# v0_3_0.net
KiCad netlist of a schematic drawn in EAGLE
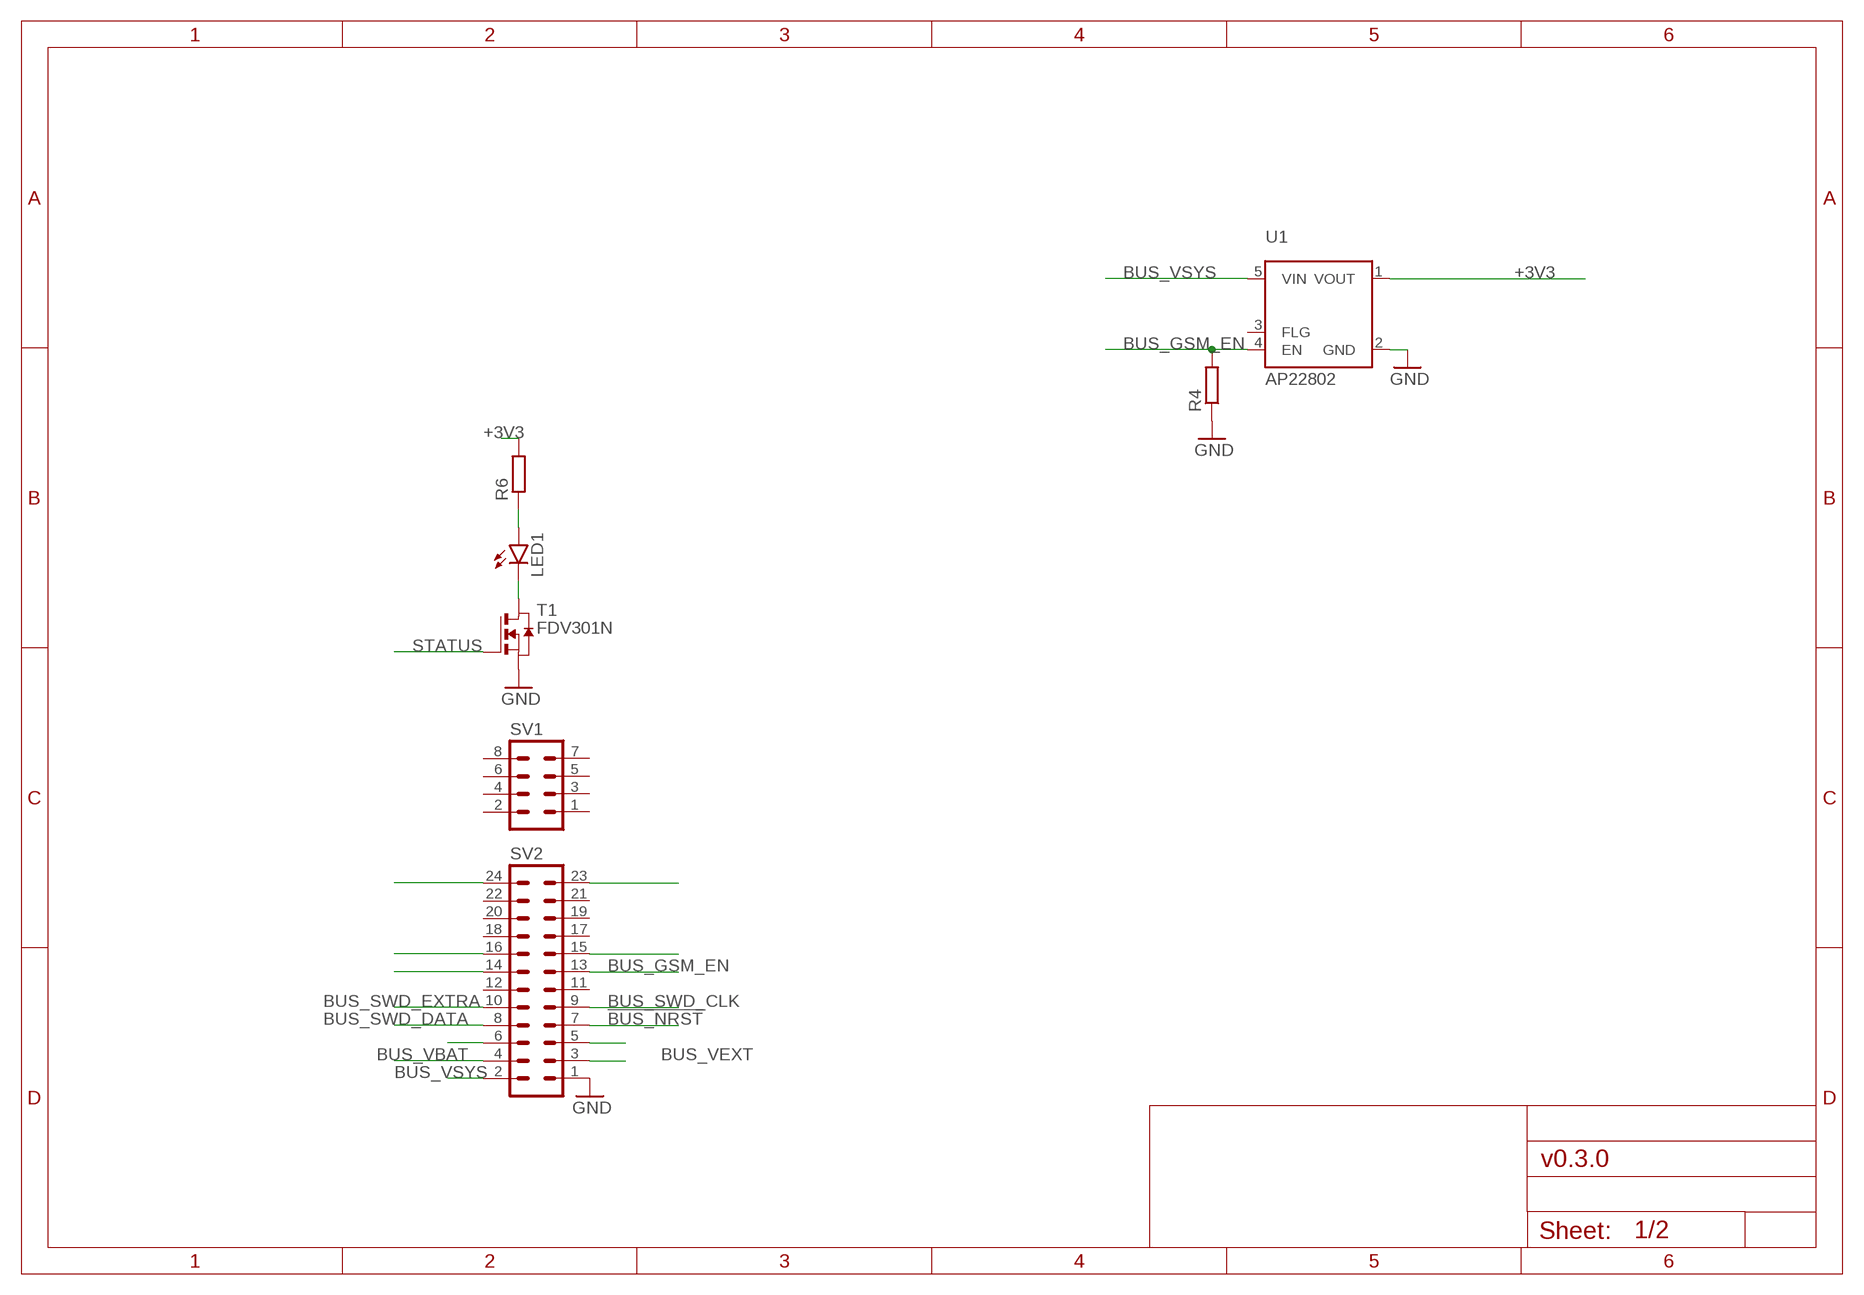
[diagram p0: schematic, sheet 1]
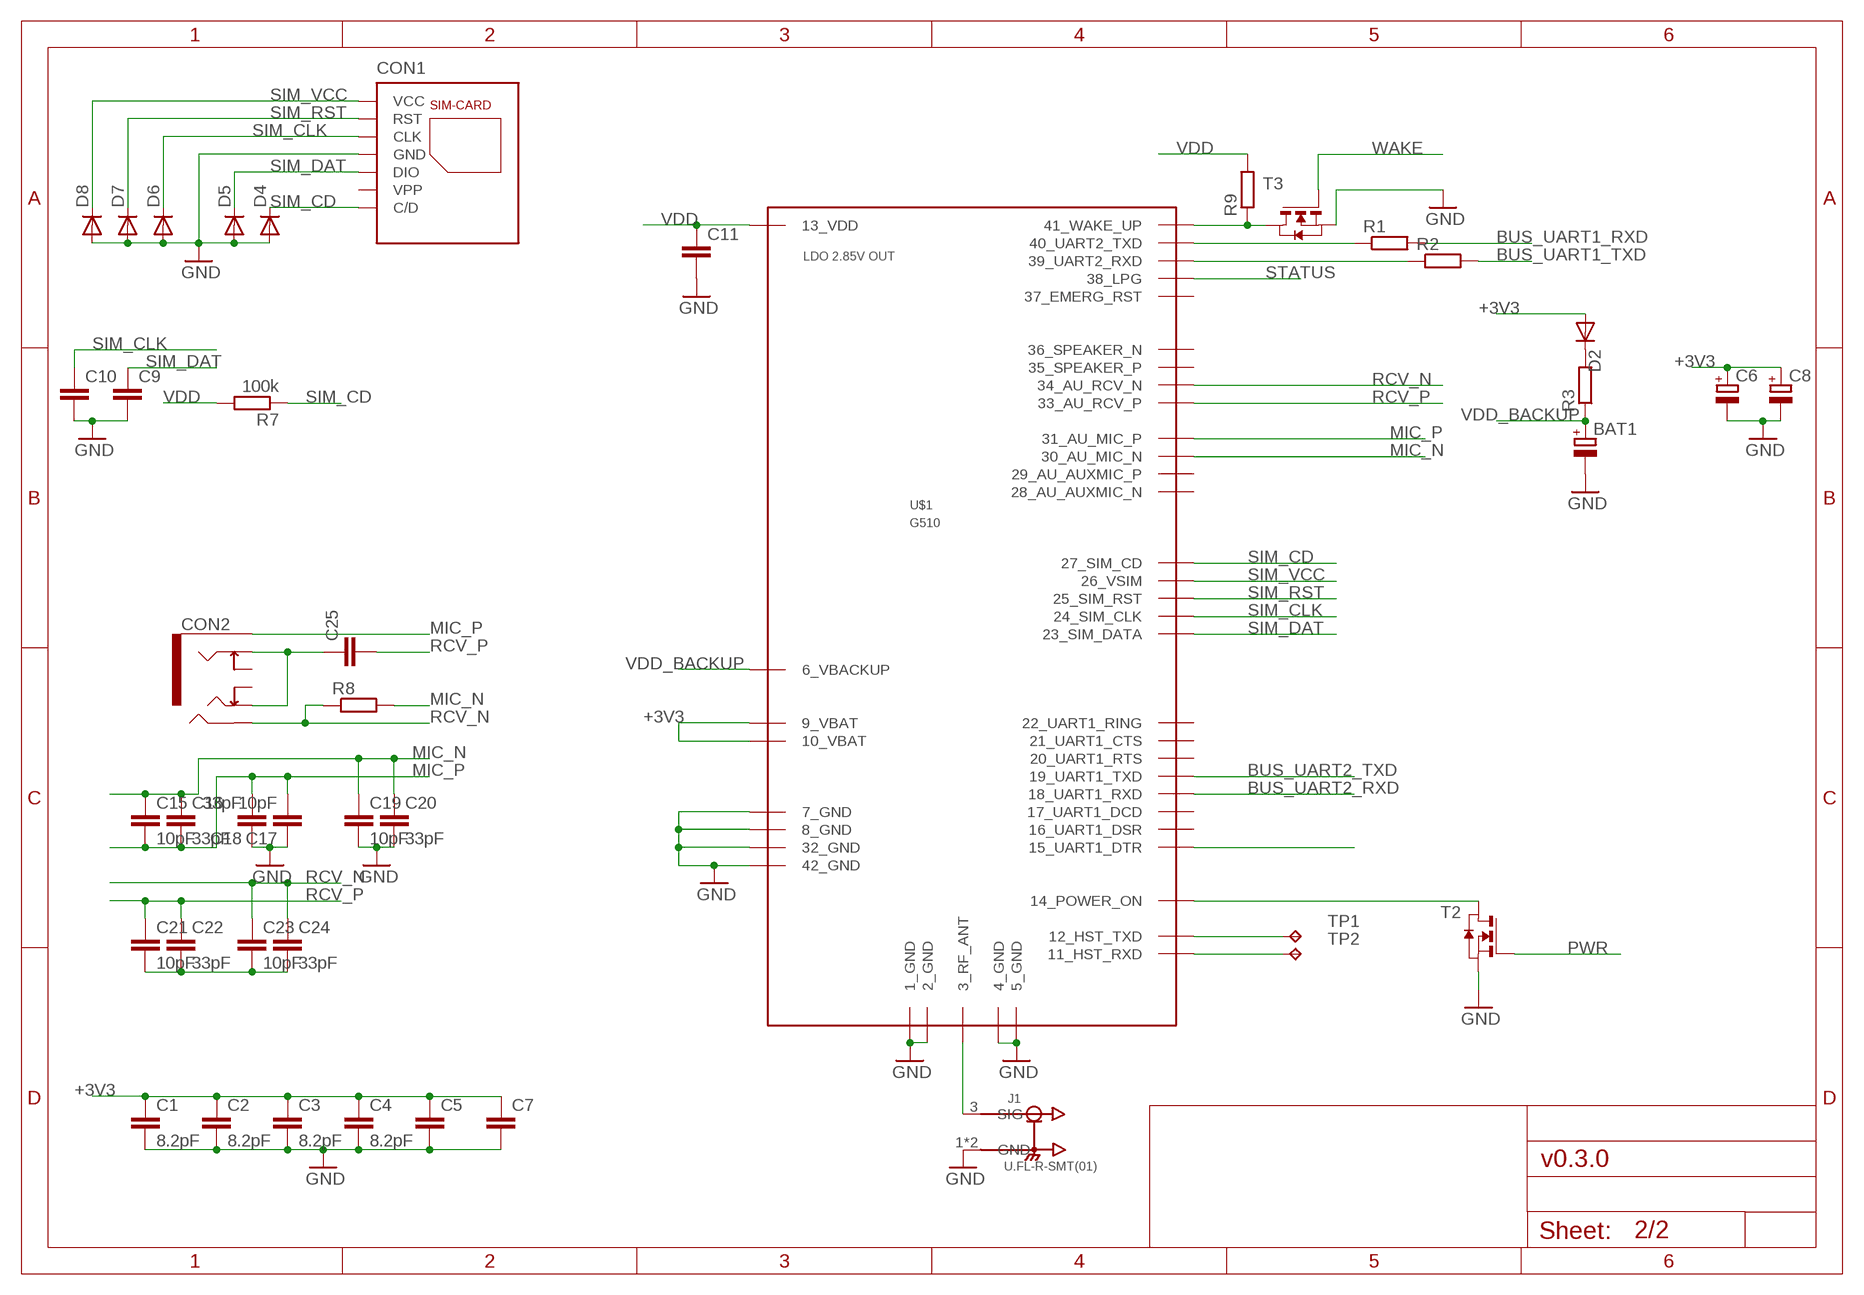
[diagram p1: schematic, sheet 2]

(export (version "E")
  (design (tool "Eeschema 10.0.6"))
  (components
    (comp (ref "BAT1")
      (value "DCK-3R3E224U-E")
      (footprint "eagle-import:621")
      (libsource (lib "eagle-import") (part "DCK-3R3E224U-E"))
    )
    (comp (ref "C1")
      (value "8.2pF")
      (footprint "eagle-import:C0402")
      (libsource (lib "eagle-import") (part "C-EUC0402"))
    )
    (comp (ref "C2")
      (value "8.2pF")
      (footprint "eagle-import:C0402")
      (libsource (lib "eagle-import") (part "C-EUC0402"))
    )
    (comp (ref "C3")
      (value "8.2pF")
      (footprint "eagle-import:C0402")
      (libsource (lib "eagle-import") (part "C-EUC0402"))
    )
    (comp (ref "C4")
      (value "8.2pF")
      (footprint "eagle-import:C0402")
      (libsource (lib "eagle-import") (part "C-EUC0402"))
    )
    (comp (ref "C5")
      (value "C-EUC0603")
      (footprint "eagle-import:C0603")
      (libsource (lib "eagle-import") (part "C-EUC0603"))
    )
    (comp (ref "C6")
      (value "CPOL-EUSMCC")
      (footprint "eagle-import:SMC_C")
      (libsource (lib "eagle-import") (part "CPOL-EUSMCC"))
    )
    (comp (ref "C7")
      (value "C-EUC0603")
      (footprint "eagle-import:C0603")
      (libsource (lib "eagle-import") (part "C-EUC0603"))
    )
    (comp (ref "C8")
      (value "CPOL-EUSMCC")
      (footprint "eagle-import:SMC_C")
      (libsource (lib "eagle-import") (part "CPOL-EUSMCC"))
    )
    (comp (ref "C9")
      (value "C-EUC0402")
      (footprint "eagle-import:C0402")
      (libsource (lib "eagle-import") (part "C-EUC0402"))
    )
    (comp (ref "C10")
      (value "C-EUC0402")
      (footprint "eagle-import:C0402")
      (libsource (lib "eagle-import") (part "C-EUC0402"))
    )
    (comp (ref "C11")
      (value "C-EUC0402")
      (footprint "eagle-import:C0402")
      (libsource (lib "eagle-import") (part "C-EUC0402"))
    )
    (comp (ref "C15")
      (value "10pF")
      (footprint "eagle-import:C0402")
      (libsource (lib "eagle-import") (part "C-EUC0402"))
    )
    (comp (ref "C16")
      (value "33pF")
      (footprint "eagle-import:C0402")
      (libsource (lib "eagle-import") (part "C-EUC0402"))
    )
    (comp (ref "C17")
      (value "10pF")
      (footprint "eagle-import:C0402")
      (libsource (lib "eagle-import") (part "C-EUC0402"))
    )
    (comp (ref "C18")
      (value "33pF")
      (footprint "eagle-import:C0402")
      (libsource (lib "eagle-import") (part "C-EUC0402"))
    )
    (comp (ref "C19")
      (value "10pF")
      (footprint "eagle-import:C0402")
      (libsource (lib "eagle-import") (part "C-EUC0402"))
    )
    (comp (ref "C20")
      (value "33pF")
      (footprint "eagle-import:C0402")
      (libsource (lib "eagle-import") (part "C-EUC0402"))
    )
    (comp (ref "C21")
      (value "10pF")
      (footprint "eagle-import:C0402")
      (libsource (lib "eagle-import") (part "C-EUC0402"))
    )
    (comp (ref "C22")
      (value "33pF")
      (footprint "eagle-import:C0402")
      (libsource (lib "eagle-import") (part "C-EUC0402"))
    )
    (comp (ref "C23")
      (value "10pF")
      (footprint "eagle-import:C0402")
      (libsource (lib "eagle-import") (part "C-EUC0402"))
    )
    (comp (ref "C24")
      (value "33pF")
      (footprint "eagle-import:C0402")
      (libsource (lib "eagle-import") (part "C-EUC0402"))
    )
    (comp (ref "C25")
      (value "C-EUC0603")
      (footprint "eagle-import:C0603")
      (libsource (lib "eagle-import") (part "C-EUC0603"))
    )
    (comp (ref "CON1")
      (value "115Q-BCA0")
      (footprint "eagle-import:115Q")
      (libsource (lib "eagle-import") (part "115Q-BCA0"))
    )
    (comp (ref "CON2")
      (value "1503-21")
      (footprint "eagle-import:150321")
      (libsource (lib "eagle-import") (part "1503-21"))
    )
    (comp (ref "D2")
      (value "DIODE-SOD323-R")
      (footprint "eagle-import:SOD323-R")
      (libsource (lib "eagle-import") (part "DIODE-SOD323-R"))
    )
    (comp (ref "D4")
      (value "DIODE-SOD323-R")
      (footprint "eagle-import:SOD323-R")
      (libsource (lib "eagle-import") (part "DIODE-SOD323-R"))
    )
    (comp (ref "D5")
      (value "DIODE-SOD323-R")
      (footprint "eagle-import:SOD323-R")
      (libsource (lib "eagle-import") (part "DIODE-SOD323-R"))
    )
    (comp (ref "D6")
      (value "DIODE-SOD323-R")
      (footprint "eagle-import:SOD323-R")
      (libsource (lib "eagle-import") (part "DIODE-SOD323-R"))
    )
    (comp (ref "D7")
      (value "DIODE-SOD323-R")
      (footprint "eagle-import:SOD323-R")
      (libsource (lib "eagle-import") (part "DIODE-SOD323-R"))
    )
    (comp (ref "D8")
      (value "DIODE-SOD323-R")
      (footprint "eagle-import:SOD323-R")
      (libsource (lib "eagle-import") (part "DIODE-SOD323-R"))
    )
    (comp (ref "J1")
      (value "U.FL-R-SMT(01)")
      (footprint "eagle-import:HRS_U.FL-R-SMT(01)")
      (fields (field (name "MF") "Hirose") (field (name "MP") "U.FL-R-SMT_01_"))
      (libsource (lib "eagle-import") (part "U.FL-R-SMT(01)"))
    )
    (comp (ref "R1")
      (value "R-EU_R0402")
      (footprint "eagle-import:R0402")
      (libsource (lib "eagle-import") (part "R-EU_R0402"))
    )
    (comp (ref "R2")
      (value "R-EU_R0402")
      (footprint "eagle-import:R0402")
      (libsource (lib "eagle-import") (part "R-EU_R0402"))
    )
    (comp (ref "R3")
      (value "R-EU_R0402")
      (footprint "eagle-import:R0402")
      (libsource (lib "eagle-import") (part "R-EU_R0402"))
    )
    (comp (ref "R7")
      (value "100k")
      (footprint "eagle-import:R0402")
      (libsource (lib "eagle-import") (part "R-EU_R0402"))
    )
    (comp (ref "R8")
      (value "R-EU_R0402")
      (footprint "eagle-import:R0402")
      (libsource (lib "eagle-import") (part "R-EU_R0402"))
    )
    (comp (ref "R9")
      (value "R-EU_R0402")
      (footprint "eagle-import:R0402")
      (libsource (lib "eagle-import") (part "R-EU_R0402"))
    )
    (comp (ref "T2")
      (value "NMOSSOT23")
      (footprint "eagle-import:SOT-23")
      (libsource (lib "eagle-import") (part "NMOSSOT23"))
    )
    (comp (ref "T3")
      (value "NMOSSOT23")
      (footprint "eagle-import:SOT-23")
      (libsource (lib "eagle-import") (part "NMOSSOT23"))
    )
    (comp (ref "TP1")
      (value "TPB1,27")
      (footprint "eagle-import:B1,27")
      (libsource (lib "eagle-import") (part "TPB1,27"))
    )
    (comp (ref "TP2")
      (value "TPB1,27")
      (footprint "eagle-import:B1,27")
      (libsource (lib "eagle-import") (part "TPB1,27"))
    )
    (comp (ref "U$1")
      (value "G510")
      (footprint "eagle-import:G510")
      (libsource (lib "eagle-import") (part "G510"))
    )
    (comp (ref "LED1")
      (value "LEDCHIP-LED0603")
      (footprint "eagle-import:CHIP-LED0603")
      (libsource (lib "eagle-import") (part "LEDCHIP-LED0603"))
    )
    (comp (ref "R4")
      (value "R-EU_R0402")
      (footprint "eagle-import:R0402")
      (libsource (lib "eagle-import") (part "R-EU_R0402"))
    )
    (comp (ref "R6")
      (value "R-EU_R0402")
      (footprint "eagle-import:R0402")
      (libsource (lib "eagle-import") (part "R-EU_R0402"))
    )
    (comp (ref "SV1")
      (value "MA04-2")
      (footprint "eagle-import:MA04-2")
      (libsource (lib "eagle-import") (part "MA04-2"))
    )
    (comp (ref "SV2")
      (value "MA12-2")
      (footprint "eagle-import:MA12-2")
      (libsource (lib "eagle-import") (part "MA12-2"))
    )
    (comp (ref "T1")
      (value "FDV301N")
      (footprint "eagle-import:SOT-23")
      (libsource (lib "eagle-import") (part "NMOSSOT23"))
    )
    (comp (ref "U1")
      (value "AP22802")
      (footprint "eagle-import:SOT25")
      (libsource (lib "eagle-import") (part "AP22802"))
    )
  )
  (nets
    (net (code "1") (name "+3V3") (class "Default")
      (node (ref "C1") (pin "1") (pinfunction "1_1") (pintype "passive"))
      (node (ref "C2") (pin "1") (pinfunction "1_1") (pintype "passive"))
      (node (ref "C3") (pin "1") (pinfunction "1_1") (pintype "passive"))
      (node (ref "C4") (pin "1") (pinfunction "1_1") (pintype "passive"))
      (node (ref "C5") (pin "1") (pinfunction "1_1") (pintype "passive"))
      (node (ref "C6") (pin "+") (pinfunction "+_+") (pintype "passive"))
      (node (ref "C7") (pin "1") (pinfunction "1_1") (pintype "passive"))
      (node (ref "C8") (pin "+") (pinfunction "+_+") (pintype "passive"))
      (node (ref "D2") (pin "A") (pinfunction "A_A") (pintype "passive"))
      (node (ref "R6") (pin "2") (pinfunction "2_2") (pintype "passive"))
      (node (ref "U$1") (pin "10_VBAT") (pinfunction "10_VBAT_10_VBAT") (pintype "power_in"))
      (node (ref "U$1") (pin "9_VBAT") (pinfunction "9_VBAT_9_VBAT") (pintype "power_in"))
      (node (ref "U1") (pin "1") (pinfunction "VOUT_1") (pintype "bidirectional"))
    )
    (net (code "2") (name "BUS_GSM_EN") (class "Default")
      (node (ref "R4") (pin "2") (pinfunction "2_2") (pintype "passive"))
      (node (ref "SV2") (pin "13") (pinfunction "13_13") (pintype "passive"))
      (node (ref "U1") (pin "4") (pinfunction "EN_4") (pintype "bidirectional"))
    )
    (net (code "3") (name "BUS_SWD_CLK") (class "Default")
      (node (ref "SV2") (pin "9") (pinfunction "9_9") (pintype "passive"))
    )
    (net (code "4") (name "BUS_SWD_DATA") (class "Default")
      (node (ref "SV2") (pin "8") (pinfunction "8_8") (pintype "passive"))
    )
    (net (code "5") (name "BUS_SWD_EXTRA") (class "Default")
      (node (ref "SV2") (pin "10") (pinfunction "10_10") (pintype "passive"))
    )
    (net (code "6") (name "BUS_UART1_RXD") (class "Default")
      (node (ref "R1") (pin "2") (pinfunction "2_2") (pintype "passive"))
    )
    (net (code "7") (name "BUS_UART1_TXD") (class "Default")
      (node (ref "R2") (pin "2") (pinfunction "2_2") (pintype "passive"))
    )
    (net (code "8") (name "BUS_UART2_RXD") (class "Default")
      (node (ref "U$1") (pin "18_UART1_RXD") (pinfunction "18_UART1_RXD_18_UART1_RXD") (pintype "input"))
    )
    (net (code "9") (name "BUS_UART2_TXD") (class "Default")
      (node (ref "U$1") (pin "19_UART1_TXD") (pinfunction "19_UART1_TXD_19_UART1_TXD") (pintype "output"))
    )
    (net (code "10") (name "BUS_VBAT") (class "Default")
      (node (ref "SV2") (pin "4") (pinfunction "4_4") (pintype "passive"))
    )
    (net (code "11") (name "BUS_VEXT") (class "Default")
      (node (ref "SV2") (pin "3") (pinfunction "3_3") (pintype "passive"))
    )
    (net (code "12") (name "BUS_VSYS") (class "Default")
      (node (ref "SV2") (pin "2") (pinfunction "2_2") (pintype "passive"))
      (node (ref "U1") (pin "5") (pinfunction "VIN_5") (pintype "bidirectional"))
    )
    (net (code "13") (name "GND") (class "Default")
      (node (ref "BAT1") (pin "-") (pinfunction "-_-") (pintype "passive"))
      (node (ref "C1") (pin "2") (pinfunction "2_2") (pintype "passive"))
      (node (ref "C10") (pin "2") (pinfunction "2_2") (pintype "passive"))
      (node (ref "C11") (pin "2") (pinfunction "2_2") (pintype "passive"))
      (node (ref "C17") (pin "1") (pinfunction "1_1") (pintype "passive"))
      (node (ref "C18") (pin "1") (pinfunction "1_1") (pintype "passive"))
      (node (ref "C19") (pin "2") (pinfunction "2_2") (pintype "passive"))
      (node (ref "C2") (pin "2") (pinfunction "2_2") (pintype "passive"))
      (node (ref "C20") (pin "2") (pinfunction "2_2") (pintype "passive"))
      (node (ref "C3") (pin "2") (pinfunction "2_2") (pintype "passive"))
      (node (ref "C4") (pin "2") (pinfunction "2_2") (pintype "passive"))
      (node (ref "C5") (pin "2") (pinfunction "2_2") (pintype "passive"))
      (node (ref "C6") (pin "-") (pinfunction "-_-") (pintype "passive"))
      (node (ref "C7") (pin "2") (pinfunction "2_2") (pintype "passive"))
      (node (ref "C8") (pin "-") (pinfunction "-_-") (pintype "passive"))
      (node (ref "C9") (pin "2") (pinfunction "2_2") (pintype "passive"))
      (node (ref "CON1") (pin "GND1") (pinfunction "GND_GND1") (pintype "passive"))
      (node (ref "CON1") (pin "GND2") (pinfunction "GND_GND2") (pintype "passive"))
      (node (ref "CON1") (pin "GND3") (pinfunction "GND_GND3") (pintype "passive"))
      (node (ref "CON1") (pin "GND4") (pinfunction "GND_GND4") (pintype "passive"))
      (node (ref "CON1") (pin "P5") (pinfunction "GND_P5") (pintype "passive"))
      (node (ref "D4") (pin "A") (pinfunction "A_A") (pintype "passive"))
      (node (ref "D5") (pin "A") (pinfunction "A_A") (pintype "passive"))
      (node (ref "D6") (pin "A") (pinfunction "A_A") (pintype "passive"))
      (node (ref "D7") (pin "A") (pinfunction "A_A") (pintype "passive"))
      (node (ref "D8") (pin "A") (pinfunction "A_A") (pintype "passive"))
      (node (ref "J1") (pin "1") (pinfunction "GND_1") (pintype "passive"))
      (node (ref "J1") (pin "2") (pinfunction "GND_2") (pintype "passive"))
      (node (ref "R4") (pin "1") (pinfunction "1_1") (pintype "passive"))
      (node (ref "SV2") (pin "1") (pinfunction "1_1") (pintype "passive"))
      (node (ref "T1") (pin "2") (pinfunction "S_2") (pintype "passive"))
      (node (ref "T2") (pin "2") (pinfunction "S_2") (pintype "passive"))
      (node (ref "T3") (pin "2") (pinfunction "S_2") (pintype "passive"))
      (node (ref "U$1") (pin "1_GND") (pinfunction "1_GND_1_GND") (pintype "power_in"))
      (node (ref "U$1") (pin "2_GND") (pinfunction "2_GND_2_GND") (pintype "power_in"))
      (node (ref "U$1") (pin "32_GND") (pinfunction "32_GND_32_GND") (pintype "power_in"))
      (node (ref "U$1") (pin "42_GND") (pinfunction "42_GND_42_GND") (pintype "power_in"))
      (node (ref "U$1") (pin "4_GND") (pinfunction "4_GND_4_GND") (pintype "power_in"))
      (node (ref "U$1") (pin "5_GND") (pinfunction "5_GND_5_GND") (pintype "power_in"))
      (node (ref "U$1") (pin "7_GND") (pinfunction "7_GND_7_GND") (pintype "power_in"))
      (node (ref "U$1") (pin "8_GND") (pinfunction "8_GND_8_GND") (pintype "power_in"))
      (node (ref "U1") (pin "2") (pinfunction "GND_2") (pintype "bidirectional"))
    )
    (net (code "14") (name "MIC_N") (class "Default")
      (node (ref "C15") (pin "1") (pinfunction "1_1") (pintype "passive"))
      (node (ref "C16") (pin "1") (pinfunction "1_1") (pintype "passive"))
      (node (ref "C19") (pin "1") (pinfunction "1_1") (pintype "passive"))
      (node (ref "C20") (pin "1") (pinfunction "1_1") (pintype "passive"))
      (node (ref "R8") (pin "2") (pinfunction "2_2") (pintype "passive"))
      (node (ref "U$1") (pin "30_AU_MIC_N") (pinfunction "30_AU_MIC_N_30_AU_MIC_N") (pintype "bidirectional"))
    )
    (net (code "15") (name "MIC_P") (class "Default")
      (node (ref "C15") (pin "2") (pinfunction "2_2") (pintype "passive"))
      (node (ref "C16") (pin "2") (pinfunction "2_2") (pintype "passive"))
      (node (ref "C17") (pin "2") (pinfunction "2_2") (pintype "passive"))
      (node (ref "C18") (pin "2") (pinfunction "2_2") (pintype "passive"))
      (node (ref "CON2") (pin "1") (pinfunction "1_1") (pintype "bidirectional"))
      (node (ref "U$1") (pin "31_AU_MIC_P") (pinfunction "31_AU_MIC_P_31_AU_MIC_P") (pintype "bidirectional"))
    )
    (net (code "16") (name "Net-(C21-Pad2)") (class "Default")
      (node (ref "C21") (pin "2") (pinfunction "2_2") (pintype "passive"))
      (node (ref "C22") (pin "2") (pinfunction "2_2") (pintype "passive"))
      (node (ref "C23") (pin "2") (pinfunction "2_2") (pintype "passive"))
      (node (ref "C24") (pin "2") (pinfunction "2_2") (pintype "passive"))
    )
    (net (code "17") (name "Net-(C25-Pad1)") (class "Default")
      (node (ref "C25") (pin "1") (pinfunction "1_1") (pintype "passive"))
      (node (ref "CON2") (pin "3") (pinfunction "3_3") (pintype "bidirectional"))
      (node (ref "CON2") (pin "5") (pinfunction "5_5") (pintype "bidirectional"))
    )
    (net (code "18") (name "Net-(D2-PadC)") (class "Default")
      (node (ref "D2") (pin "C") (pinfunction "C_C") (pintype "passive"))
      (node (ref "R3") (pin "2") (pinfunction "2_2") (pintype "passive"))
    )
    (net (code "19") (name "Net-(J1-SIG)") (class "Default")
      (node (ref "J1") (pin "3") (pinfunction "SIG_3") (pintype "passive"))
      (node (ref "U$1") (pin "3_RF_ANT") (pinfunction "3_RF_ANT_3_RF_ANT") (pintype "bidirectional"))
    )
    (net (code "20") (name "Net-(LED1-PadA)") (class "Default")
      (node (ref "LED1") (pin "A") (pinfunction "A_A") (pintype "passive"))
      (node (ref "R6") (pin "1") (pinfunction "1_1") (pintype "passive"))
    )
    (net (code "21") (name "Net-(R1-Pad1)") (class "Default")
      (node (ref "R1") (pin "1") (pinfunction "1_1") (pintype "passive"))
      (node (ref "U$1") (pin "40_UART2_TXD") (pinfunction "40_UART2_TXD_40_UART2_TXD") (pintype "output"))
    )
    (net (code "22") (name "Net-(R2-Pad1)") (class "Default")
      (node (ref "R2") (pin "1") (pinfunction "1_1") (pintype "passive"))
      (node (ref "U$1") (pin "39_UART2_RXD") (pinfunction "39_UART2_RXD_39_UART2_RXD") (pintype "input"))
    )
    (net (code "23") (name "Net-(T1-D)") (class "Default")
      (node (ref "LED1") (pin "C") (pinfunction "C_C") (pintype "passive"))
      (node (ref "T1") (pin "1") (pinfunction "D_1") (pintype "passive"))
    )
    (net (code "24") (name "Net-(T2-D)") (class "Default")
      (node (ref "T2") (pin "1") (pinfunction "D_1") (pintype "passive"))
      (node (ref "U$1") (pin "14_POWER_ON") (pinfunction "14_POWER_ON_14_POWER_ON") (pintype "input"))
    )
    (net (code "25") (name "Net-(T3-D)") (class "Default")
      (node (ref "R9") (pin "1") (pinfunction "1_1") (pintype "passive"))
      (node (ref "T3") (pin "1") (pinfunction "D_1") (pintype "passive"))
      (node (ref "U$1") (pin "41_WAKE_UP") (pinfunction "41_WAKE_UP_41_WAKE_UP") (pintype "bidirectional"))
    )
    (net (code "26") (name "Net-(TP1-PadTP)") (class "Default")
      (node (ref "TP1") (pin "TP") (pinfunction "TP_TP") (pintype "input"))
      (node (ref "U$1") (pin "12_HST_TXD") (pinfunction "12_HST_TXD_12_HST_TXD") (pintype "output"))
    )
    (net (code "27") (name "Net-(U$1-11_HST_RXD)") (class "Default")
      (node (ref "TP2") (pin "TP") (pinfunction "TP_TP") (pintype "input"))
      (node (ref "U$1") (pin "11_HSTRXD") (pinfunction "11_HST_RXD_11_HSTRXD") (pintype "input"))
    )
    (net (code "28") (name "PWR") (class "Default")
      (node (ref "T2") (pin "3") (pinfunction "G_3") (pintype "passive"))
    )
    (net (code "29") (name "RCV_N") (class "Default")
      (node (ref "C23") (pin "1") (pinfunction "1_1") (pintype "passive"))
      (node (ref "C24") (pin "1") (pinfunction "1_1") (pintype "passive"))
      (node (ref "CON2") (pin "2") (pinfunction "2_2") (pintype "bidirectional"))
      (node (ref "R8") (pin "1") (pinfunction "1_1") (pintype "passive"))
      (node (ref "U$1") (pin "34_AU_RCV_N") (pinfunction "34_AU_RCV_N_34_AU_RCV_N") (pintype "bidirectional"))
    )
    (net (code "30") (name "RCV_P") (class "Default")
      (node (ref "C21") (pin "1") (pinfunction "1_1") (pintype "passive"))
      (node (ref "C22") (pin "1") (pinfunction "1_1") (pintype "passive"))
      (node (ref "C25") (pin "2") (pinfunction "2_2") (pintype "passive"))
      (node (ref "U$1") (pin "33_AU_RCV_P") (pinfunction "33_AU_RCV_P_33_AU_RCV_P") (pintype "bidirectional"))
    )
    (net (code "31") (name "SIM_CD") (class "Default")
      (node (ref "CON1") (pin "CD") (pinfunction "C/D_CD") (pintype "passive"))
      (node (ref "D4") (pin "C") (pinfunction "C_C") (pintype "passive"))
      (node (ref "R7") (pin "1") (pinfunction "1_1") (pintype "passive"))
      (node (ref "U$1") (pin "27_SIM_CD") (pinfunction "27_SIM_CD_27_SIM_CD") (pintype "bidirectional"))
    )
    (net (code "32") (name "SIM_CLK") (class "Default")
      (node (ref "C10") (pin "1") (pinfunction "1_1") (pintype "passive"))
      (node (ref "CON1") (pin "P3") (pinfunction "CLK_P3") (pintype "passive"))
      (node (ref "D6") (pin "C") (pinfunction "C_C") (pintype "passive"))
      (node (ref "U$1") (pin "24_SIM_CLK") (pinfunction "24_SIM_CLK_24_SIM_CLK") (pintype "bidirectional"))
    )
    (net (code "33") (name "SIM_DAT") (class "Default")
      (node (ref "C9") (pin "1") (pinfunction "1_1") (pintype "passive"))
      (node (ref "CON1") (pin "P7") (pinfunction "DIO_P7") (pintype "passive"))
      (node (ref "D5") (pin "C") (pinfunction "C_C") (pintype "passive"))
      (node (ref "U$1") (pin "23_SIM_DATA") (pinfunction "23_SIM_DATA_23_SIM_DATA") (pintype "bidirectional"))
    )
    (net (code "34") (name "SIM_RST") (class "Default")
      (node (ref "CON1") (pin "P2") (pinfunction "RST_P2") (pintype "passive"))
      (node (ref "D7") (pin "C") (pinfunction "C_C") (pintype "passive"))
      (node (ref "U$1") (pin "25_SIM_RST") (pinfunction "25_SIM_RST_25_SIM_RST") (pintype "bidirectional"))
    )
    (net (code "35") (name "SIM_VCC") (class "Default")
      (node (ref "CON1") (pin "P1") (pinfunction "VCC_P1") (pintype "passive"))
      (node (ref "D8") (pin "C") (pinfunction "C_C") (pintype "passive"))
      (node (ref "U$1") (pin "26_VSIM") (pinfunction "26_VSIM_26_VSIM") (pintype "bidirectional"))
    )
    (net (code "36") (name "STATUS") (class "Default")
      (node (ref "T1") (pin "3") (pinfunction "G_3") (pintype "passive"))
      (node (ref "U$1") (pin "38_LPG") (pinfunction "38_LPG_38_LPG") (pintype "output"))
    )
    (net (code "37") (name "VDD") (class "Default")
      (node (ref "C11") (pin "1") (pinfunction "1_1") (pintype "passive"))
      (node (ref "R7") (pin "2") (pinfunction "2_2") (pintype "passive"))
      (node (ref "R9") (pin "2") (pinfunction "2_2") (pintype "passive"))
      (node (ref "U$1") (pin "13_VDD") (pinfunction "13_VDD_13_VDD") (pintype "power_in"))
    )
    (net (code "38") (name "VDD_BACKUP") (class "Default")
      (node (ref "BAT1") (pin "+") (pinfunction "+_+") (pintype "passive"))
      (node (ref "R3") (pin "1") (pinfunction "1_1") (pintype "passive"))
      (node (ref "U$1") (pin "6_VBACKUP") (pinfunction "6_VBACKUP_6_VBACKUP") (pintype "power_in"))
    )
    (net (code "39") (name "WAKE") (class "Default")
      (node (ref "T3") (pin "3") (pinfunction "G_3") (pintype "passive"))
    )
    (net (code "40") (name "unconnected-(CON1-VPP-PadP6)") (class "Default")
      (node (ref "CON1") (pin "P6") (pinfunction "VPP_P6") (pintype "passive"))
    )
    (net (code "41") (name "unconnected-(CON2-Pad4)") (class "Default")
      (node (ref "CON2") (pin "4") (pinfunction "4_4") (pintype "bidirectional"))
    )
    (net (code "42") (name "unconnected-(CON2-Pad6)") (class "Default")
      (node (ref "CON2") (pin "6") (pinfunction "6_6") (pintype "bidirectional"))
    )
    (net (code "43") (name "unconnected-(SV1-Pad1)") (class "Default")
      (node (ref "SV1") (pin "1") (pinfunction "1_1") (pintype "passive"))
    )
    (net (code "44") (name "unconnected-(SV1-Pad2)") (class "Default")
      (node (ref "SV1") (pin "2") (pinfunction "2_2") (pintype "passive"))
    )
    (net (code "45") (name "unconnected-(SV1-Pad3)") (class "Default")
      (node (ref "SV1") (pin "3") (pinfunction "3_3") (pintype "passive"))
    )
    (net (code "46") (name "unconnected-(SV1-Pad4)") (class "Default")
      (node (ref "SV1") (pin "4") (pinfunction "4_4") (pintype "passive"))
    )
    (net (code "47") (name "unconnected-(SV1-Pad5)") (class "Default")
      (node (ref "SV1") (pin "5") (pinfunction "5_5") (pintype "passive"))
    )
    (net (code "48") (name "unconnected-(SV1-Pad6)") (class "Default")
      (node (ref "SV1") (pin "6") (pinfunction "6_6") (pintype "passive"))
    )
    (net (code "49") (name "unconnected-(SV1-Pad7)") (class "Default")
      (node (ref "SV1") (pin "7") (pinfunction "7_7") (pintype "passive"))
    )
    (net (code "50") (name "unconnected-(SV1-Pad8)") (class "Default")
      (node (ref "SV1") (pin "8") (pinfunction "8_8") (pintype "passive"))
    )
    (net (code "51") (name "unconnected-(SV2-Pad5)") (class "Default")
      (node (ref "SV2") (pin "5") (pinfunction "5_5") (pintype "passive"))
    )
    (net (code "52") (name "unconnected-(SV2-Pad6)") (class "Default")
      (node (ref "SV2") (pin "6") (pinfunction "6_6") (pintype "passive"))
    )
    (net (code "53") (name "unconnected-(SV2-Pad11)") (class "Default")
      (node (ref "SV2") (pin "11") (pinfunction "11_11") (pintype "passive"))
    )
    (net (code "54") (name "unconnected-(SV2-Pad12)") (class "Default")
      (node (ref "SV2") (pin "12") (pinfunction "12_12") (pintype "passive"))
    )
    (net (code "55") (name "unconnected-(SV2-Pad14)") (class "Default")
      (node (ref "SV2") (pin "14") (pinfunction "14_14") (pintype "passive"))
    )
    (net (code "56") (name "unconnected-(SV2-Pad15)") (class "Default")
      (node (ref "SV2") (pin "15") (pinfunction "15_15") (pintype "passive"))
    )
    (net (code "57") (name "unconnected-(SV2-Pad16)") (class "Default")
      (node (ref "SV2") (pin "16") (pinfunction "16_16") (pintype "passive"))
    )
    (net (code "58") (name "unconnected-(SV2-Pad17)") (class "Default")
      (node (ref "SV2") (pin "17") (pinfunction "17_17") (pintype "passive"))
    )
    (net (code "59") (name "unconnected-(SV2-Pad18)") (class "Default")
      (node (ref "SV2") (pin "18") (pinfunction "18_18") (pintype "passive"))
    )
    (net (code "60") (name "unconnected-(SV2-Pad19)") (class "Default")
      (node (ref "SV2") (pin "19") (pinfunction "19_19") (pintype "passive"))
    )
    (net (code "61") (name "unconnected-(SV2-Pad20)") (class "Default")
      (node (ref "SV2") (pin "20") (pinfunction "20_20") (pintype "passive"))
    )
    (net (code "62") (name "unconnected-(SV2-Pad21)") (class "Default")
      (node (ref "SV2") (pin "21") (pinfunction "21_21") (pintype "passive"))
    )
    (net (code "63") (name "unconnected-(SV2-Pad22)") (class "Default")
      (node (ref "SV2") (pin "22") (pinfunction "22_22") (pintype "passive"))
    )
    (net (code "64") (name "unconnected-(SV2-Pad23)") (class "Default")
      (node (ref "SV2") (pin "23") (pinfunction "23_23") (pintype "passive"))
    )
    (net (code "65") (name "unconnected-(SV2-Pad24)") (class "Default")
      (node (ref "SV2") (pin "24") (pinfunction "24_24") (pintype "passive"))
    )
    (net (code "66") (name "unconnected-(U$1-Pad15_UART1_DTR)") (class "Default")
      (node (ref "U$1") (pin "15_UART1_DTR") (pinfunction "15_UART1_DTR_15_UART1_DTR") (pintype "bidirectional"))
    )
    (net (code "67") (name "unconnected-(U$1-Pad16_UART1_DSR)") (class "Default")
      (node (ref "U$1") (pin "16_UART1_DSR") (pinfunction "16_UART1_DSR_16_UART1_DSR") (pintype "bidirectional"))
    )
    (net (code "68") (name "unconnected-(U$1-Pad17_UART1_DCD)") (class "Default")
      (node (ref "U$1") (pin "17_UART1_DCD") (pinfunction "17_UART1_DCD_17_UART1_DCD") (pintype "bidirectional"))
    )
    (net (code "69") (name "unconnected-(U$1-Pad20_UART1_RTS)") (class "Default")
      (node (ref "U$1") (pin "20_UART1_RTS") (pinfunction "20_UART1_RTS_20_UART1_RTS") (pintype "bidirectional"))
    )
    (net (code "70") (name "unconnected-(U$1-Pad21_UART1_CTS)") (class "Default")
      (node (ref "U$1") (pin "21_UART1_CTS") (pinfunction "21_UART1_CTS_21_UART1_CTS") (pintype "bidirectional"))
    )
    (net (code "71") (name "unconnected-(U$1-Pad22_UART1_RING)") (class "Default")
      (node (ref "U$1") (pin "22_UART1_RING") (pinfunction "22_UART1_RING_22_UART1_RING") (pintype "bidirectional"))
    )
    (net (code "72") (name "unconnected-(U$1-Pad28_AU_AUXMIC_N)") (class "Default")
      (node (ref "U$1") (pin "28_AU_AUXMIC_N") (pinfunction "28_AU_AUXMIC_N_28_AU_AUXMIC_N") (pintype "bidirectional"))
    )
    (net (code "73") (name "unconnected-(U$1-Pad29_AU_AUXMIC_P)") (class "Default")
      (node (ref "U$1") (pin "29_AU_AUXMIC_P") (pinfunction "29_AU_AUXMIC_P_29_AU_AUXMIC_P") (pintype "bidirectional"))
    )
    (net (code "74") (name "unconnected-(U$1-Pad35_SPEAKER_P)") (class "Default")
      (node (ref "U$1") (pin "35_SPEAKER_P") (pinfunction "35_SPEAKER_P_35_SPEAKER_P") (pintype "bidirectional"))
    )
    (net (code "75") (name "unconnected-(U$1-Pad36_SPEAKER_N)") (class "Default")
      (node (ref "U$1") (pin "36_SPEAKER_N") (pinfunction "36_SPEAKER_N_36_SPEAKER_N") (pintype "bidirectional"))
    )
    (net (code "76") (name "unconnected-(U$1-Pad37_EMERG_RST)") (class "Default")
      (node (ref "U$1") (pin "37_EMERG_RST") (pinfunction "37_EMERG_RST_37_EMERG_RST") (pintype "input"))
    )
    (net (code "77") (name "unconnected-(U1-FLG-Pad3)") (class "Default")
      (node (ref "U1") (pin "3") (pinfunction "FLG_3") (pintype "bidirectional"))
    )
    (net (code "78") (name "~{BUS_NRST}") (class "Default")
      (node (ref "SV2") (pin "7") (pinfunction "7_7") (pintype "passive"))
    )
  )
)
